# btm_minibord.net
KiCad netlist of a schematic drawn in EAGLE
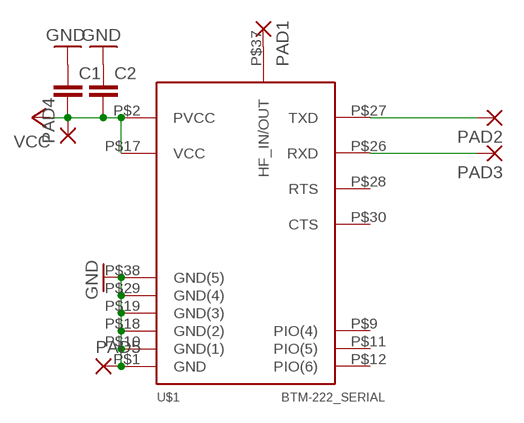
[diagram p0: schematic, sheet 1]

(export (version "E")
  (design (tool "Eeschema 10.0.6"))
  (components
    (comp (ref "C1")
      (value "C-EUC0805")
      (footprint "eagle-import:C0805")
      (libsource (lib "eagle-import") (part "C-EUC0805"))
    )
    (comp (ref "C2")
      (value "C-EUC0805")
      (footprint "eagle-import:C0805")
      (libsource (lib "eagle-import") (part "C-EUC0805"))
    )
    (comp (ref "PAD1")
      (value "1,6/0,8")
      (footprint "eagle-import:1,6_0,8")
      (libsource (lib "eagle-import") (part "1,6/0,8"))
    )
    (comp (ref "PAD2")
      (value "1,6/0,8")
      (footprint "eagle-import:1,6_0,8")
      (libsource (lib "eagle-import") (part "1,6/0,8"))
    )
    (comp (ref "PAD3")
      (value "1,6/0,8")
      (footprint "eagle-import:1,6_0,8")
      (libsource (lib "eagle-import") (part "1,6/0,8"))
    )
    (comp (ref "PAD4")
      (value "1,6/0,8")
      (footprint "eagle-import:1,6_0,8")
      (libsource (lib "eagle-import") (part "1,6/0,8"))
    )
    (comp (ref "PAD5")
      (value "1,6/0,8")
      (footprint "eagle-import:1,6_0,8")
      (libsource (lib "eagle-import") (part "1,6/0,8"))
    )
    (comp (ref "U$1")
      (value "BTM-222_SERIAL")
      (footprint "eagle-import:BTM-222")
      (libsource (lib "eagle-import") (part "BTM-222_SERIAL"))
    )
  )
  (nets
    (net (code "1") (name "GND") (class "Default")
      (node (ref "C1") (pin "1") (pinfunction "1_1") (pintype "passive"))
      (node (ref "C2") (pin "1") (pinfunction "1_1") (pintype "passive"))
      (node (ref "PAD5") (pin "1") (pinfunction "P_1") (pintype "passive"))
      (node (ref "U$1") (pin "P$1") (pinfunction "GND_P$1") (pintype "bidirectional"))
      (node (ref "U$1") (pin "P$10") (pinfunction "GND(1)_P$10") (pintype "power_in"))
      (node (ref "U$1") (pin "P$18") (pinfunction "GND(2)_P$18") (pintype "bidirectional"))
      (node (ref "U$1") (pin "P$19") (pinfunction "GND(3)_P$19") (pintype "bidirectional"))
      (node (ref "U$1") (pin "P$29") (pinfunction "GND(4)_P$29") (pintype "bidirectional"))
      (node (ref "U$1") (pin "P$38") (pinfunction "GND(5)_P$38") (pintype "bidirectional"))
    )
    (net (code "2") (name "Net-(PAD1-P)") (class "Default")
      (node (ref "PAD1") (pin "1") (pinfunction "P_1") (pintype "passive"))
      (node (ref "U$1") (pin "P$37") (pinfunction "HF_IN/OUT_P$37") (pintype "bidirectional"))
    )
    (net (code "3") (name "Net-(PAD2-P)") (class "Default")
      (node (ref "PAD2") (pin "1") (pinfunction "P_1") (pintype "passive"))
      (node (ref "U$1") (pin "P$27") (pinfunction "TXD_P$27") (pintype "bidirectional"))
    )
    (net (code "4") (name "Net-(PAD3-P)") (class "Default")
      (node (ref "PAD3") (pin "1") (pinfunction "P_1") (pintype "passive"))
      (node (ref "U$1") (pin "P$26") (pinfunction "RXD_P$26") (pintype "bidirectional"))
    )
    (net (code "5") (name "VCC") (class "Default")
      (node (ref "C1") (pin "2") (pinfunction "2_2") (pintype "passive"))
      (node (ref "C2") (pin "2") (pinfunction "2_2") (pintype "passive"))
      (node (ref "PAD4") (pin "1") (pinfunction "P_1") (pintype "passive"))
      (node (ref "U$1") (pin "P$17") (pinfunction "VCC_P$17") (pintype "power_in"))
      (node (ref "U$1") (pin "P$2") (pinfunction "PVCC_P$2") (pintype "power_in"))
    )
    (net (code "6") (name "unconnected-(U$1-CTS-PadP$30)") (class "Default")
      (node (ref "U$1") (pin "P$30") (pinfunction "CTS_P$30") (pintype "bidirectional"))
    )
    (net (code "7") (name "unconnected-(U$1-PIO(4)-PadP$9)") (class "Default")
      (node (ref "U$1") (pin "P$9") (pinfunction "PIO(4)_P$9") (pintype "bidirectional"))
    )
    (net (code "8") (name "unconnected-(U$1-PIO(5)-PadP$11)") (class "Default")
      (node (ref "U$1") (pin "P$11") (pinfunction "PIO(5)_P$11") (pintype "bidirectional"))
    )
    (net (code "9") (name "unconnected-(U$1-PIO(6)-PadP$12)") (class "Default")
      (node (ref "U$1") (pin "P$12") (pinfunction "PIO(6)_P$12") (pintype "bidirectional"))
    )
    (net (code "10") (name "unconnected-(U$1-RTS-PadP$28)") (class "Default")
      (node (ref "U$1") (pin "P$28") (pinfunction "RTS_P$28") (pintype "bidirectional"))
    )
  )
)
